# SCH_chris-dual-hd-connector-v3_2021-12-0.net
KiCad netlist of a schematic drawn in EasyEDA
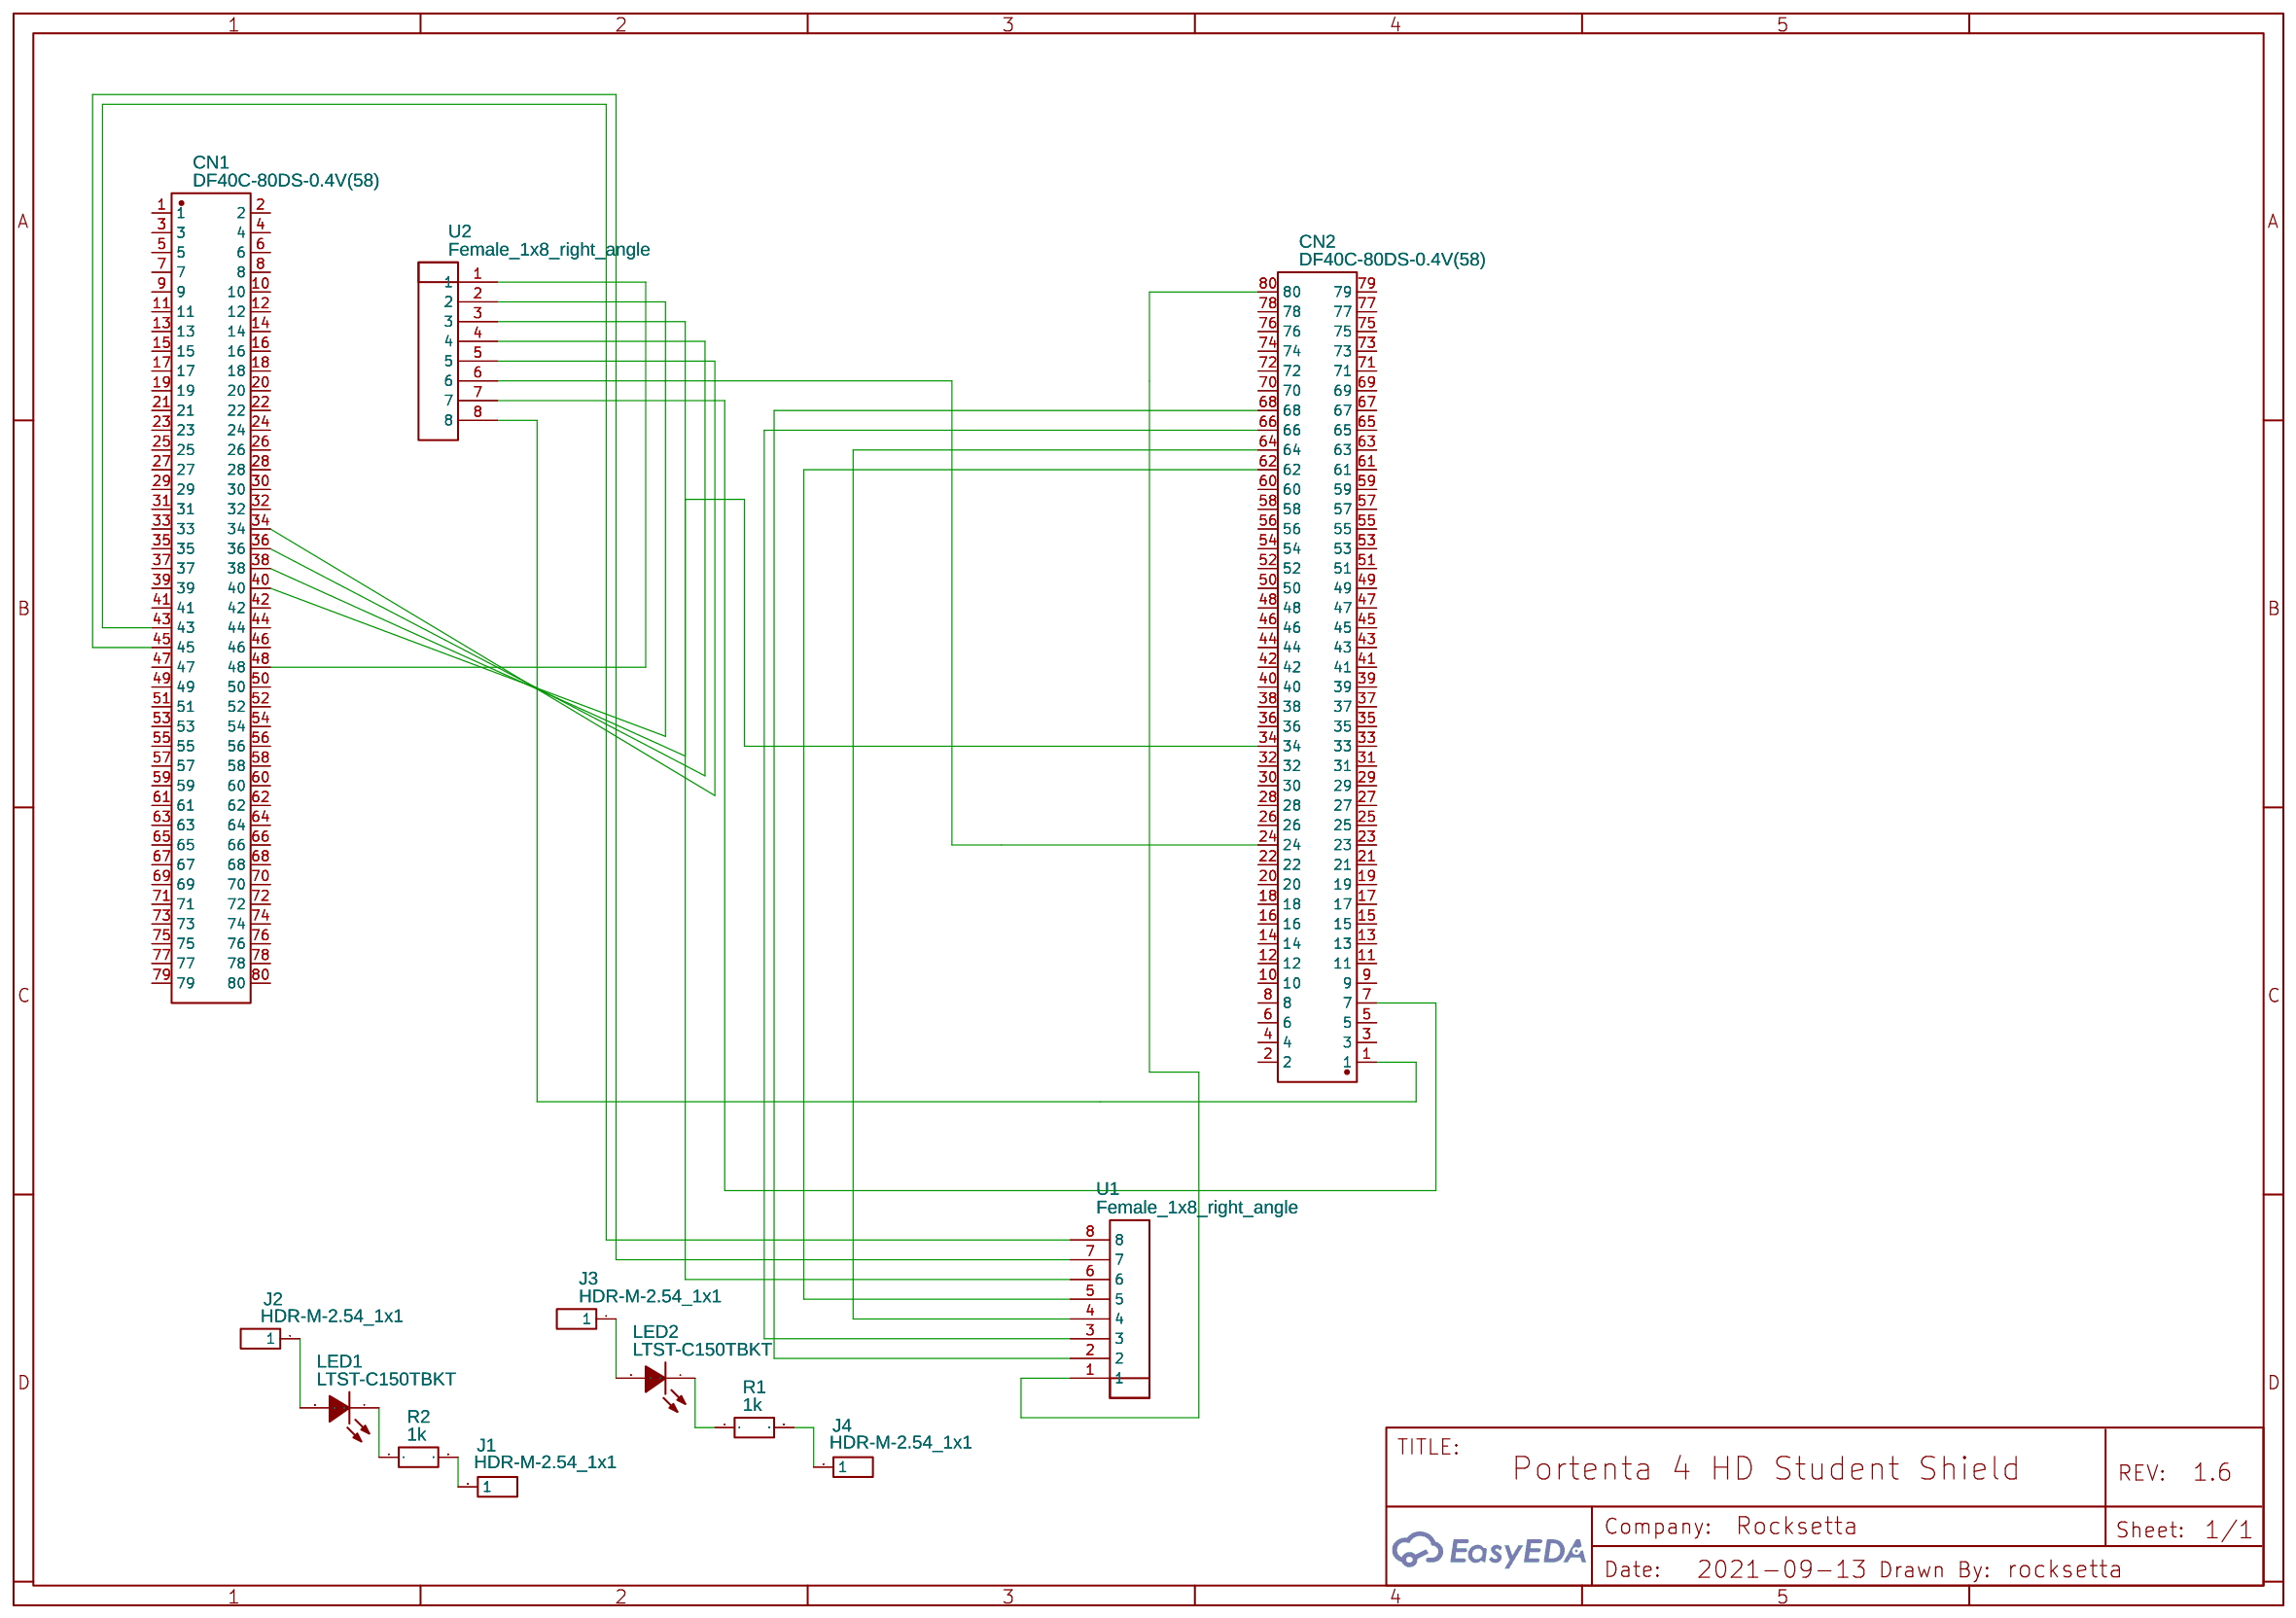
[diagram p0: schematic sheet]

(export (version "E")
  (design (tool "Eeschema 10.0.6"))
  (components
    (comp (ref "CN1")
      (value "DF40C-80DS-0.4V(58)")
      (fields (field (name "BOM_Supplier Part") "C597941"))
      (libsource (lib "") (part "DF40C-80DS-0.4V(58)_1"))
    )
    (comp (ref "CN2")
      (value "DF40C-80DS-0.4V(58)")
      (fields (field (name "BOM_Supplier Part") "C597941"))
      (libsource (lib "") (part "DF40C-80DS-0.4V(58)"))
    )
    (comp (ref "J1")
      (value "HDR-M-2.54_1x1")
      (fields (field (name "BOM_Supplier Part") "C81276"))
      (libsource (lib "") (part "HDR-M-2.54_1x1"))
    )
    (comp (ref "J2")
      (value "HDR-M-2.54_1x1")
      (fields (field (name "BOM_Supplier Part") "C81276"))
      (libsource (lib "") (part "HDR-M-2.54_1x1_1"))
    )
    (comp (ref "J3")
      (value "HDR-M-2.54_1x1")
      (fields (field (name "BOM_Supplier Part") "C81276"))
      (libsource (lib "") (part "HDR-M-2.54_1x1_1"))
    )
    (comp (ref "J4")
      (value "HDR-M-2.54_1x1")
      (fields (field (name "BOM_Supplier Part") "C81276"))
      (libsource (lib "") (part "HDR-M-2.54_1x1"))
    )
    (comp (ref "LED1")
      (value "LTST-C150TBKT")
      (fields (field (name "BOM_Supplier Part") "C125088"))
      (libsource (lib "") (part "LTST-C150TBKT"))
    )
    (comp (ref "LED2")
      (value "LTST-C150TBKT")
      (fields (field (name "BOM_Supplier Part") "C125088"))
      (libsource (lib "") (part "LTST-C150TBKT"))
    )
    (comp (ref "R1") (value "1k") (libsource (lib "") (part "R_0805_EU")))
    (comp (ref "R2") (value "1k") (libsource (lib "") (part "R_0805_EU")))
    (comp (ref "U1")
      (value "Female_1x8_right_angle")
      (fields
        (field (name "BOM_Manufacturer Part") "PPPC081LGBN-RC")
        (field (name "BOM_Supplier Part") "S5483-ND")
      )
      (libsource (lib "") (part "Female_1x8_right_angle_1"))
    )
    (comp (ref "U2")
      (value "Female_1x8_right_angle")
      (fields
        (field (name "BOM_Manufacturer Part") "PPPC081LGBN-RC")
        (field (name "BOM_Supplier Part") "S5483-ND")
      )
      (libsource (lib "") (part "Female_1x8_right_angle"))
    )
  )
  (nets
    (net (code "1") (name "Net-(CN1-Pad34)") (class "Default")
      (node (ref "CN1") (pin "34") (pinfunction "34_34") (pintype "unspecified"))
      (node (ref "U2") (pin "5") (pinfunction "5_5") (pintype "unspecified"))
    )
    (net (code "2") (name "Net-(CN1-Pad36)") (class "Default")
      (node (ref "CN1") (pin "36") (pinfunction "36_36") (pintype "unspecified"))
      (node (ref "U2") (pin "4") (pinfunction "4_4") (pintype "unspecified"))
    )
    (net (code "3") (name "Net-(CN1-Pad38)") (class "Default")
      (node (ref "CN1") (pin "38") (pinfunction "38_38") (pintype "unspecified"))
      (node (ref "U2") (pin "3") (pinfunction "3_3") (pintype "unspecified"))
    )
    (net (code "4") (name "Net-(CN1-Pad40)") (class "Default")
      (node (ref "CN1") (pin "40") (pinfunction "40_40") (pintype "unspecified"))
      (node (ref "U2") (pin "2") (pinfunction "2_2") (pintype "unspecified"))
    )
    (net (code "5") (name "Net-(CN1-Pad43)") (class "Default")
      (node (ref "CN1") (pin "43") (pinfunction "43_43") (pintype "unspecified"))
      (node (ref "U1") (pin "8") (pinfunction "8_8") (pintype "unspecified"))
    )
    (net (code "6") (name "Net-(CN1-Pad45)") (class "Default")
      (node (ref "CN1") (pin "45") (pinfunction "45_45") (pintype "unspecified"))
      (node (ref "U1") (pin "7") (pinfunction "7_7") (pintype "unspecified"))
    )
    (net (code "7") (name "Net-(CN1-Pad48)") (class "Default")
      (node (ref "CN1") (pin "48") (pinfunction "48_48") (pintype "unspecified"))
      (node (ref "U2") (pin "1") (pinfunction "1_1") (pintype "unspecified"))
    )
    (net (code "8") (name "Net-(CN2-Pad1)") (class "Default")
      (node (ref "CN2") (pin "1") (pinfunction "1_1") (pintype "unspecified"))
      (node (ref "U2") (pin "8") (pinfunction "8_8") (pintype "unspecified"))
    )
    (net (code "9") (name "Net-(CN2-Pad7)") (class "Default")
      (node (ref "CN2") (pin "7") (pinfunction "7_7") (pintype "unspecified"))
      (node (ref "U2") (pin "7") (pinfunction "7_7") (pintype "unspecified"))
    )
    (net (code "10") (name "Net-(CN2-Pad24)") (class "Default")
      (node (ref "CN2") (pin "24") (pinfunction "24_24") (pintype "unspecified"))
      (node (ref "U2") (pin "6") (pinfunction "6_6") (pintype "unspecified"))
    )
    (net (code "11") (name "Net-(CN2-Pad34)") (class "Default")
      (node (ref "CN2") (pin "34") (pinfunction "34_34") (pintype "unspecified"))
      (node (ref "U1") (pin "6") (pinfunction "6_6") (pintype "unspecified"))
    )
    (net (code "12") (name "Net-(CN2-Pad62)") (class "Default")
      (node (ref "CN2") (pin "62") (pinfunction "62_62") (pintype "unspecified"))
      (node (ref "U1") (pin "5") (pinfunction "5_5") (pintype "unspecified"))
    )
    (net (code "13") (name "Net-(CN2-Pad64)") (class "Default")
      (node (ref "CN2") (pin "64") (pinfunction "64_64") (pintype "unspecified"))
      (node (ref "U1") (pin "4") (pinfunction "4_4") (pintype "unspecified"))
    )
    (net (code "14") (name "Net-(CN2-Pad66)") (class "Default")
      (node (ref "CN2") (pin "66") (pinfunction "66_66") (pintype "unspecified"))
      (node (ref "U1") (pin "3") (pinfunction "3_3") (pintype "unspecified"))
    )
    (net (code "15") (name "Net-(CN2-Pad68)") (class "Default")
      (node (ref "CN2") (pin "68") (pinfunction "68_68") (pintype "unspecified"))
      (node (ref "U1") (pin "2") (pinfunction "2_2") (pintype "unspecified"))
    )
    (net (code "16") (name "Net-(CN2-Pad80)") (class "Default")
      (node (ref "CN2") (pin "80") (pinfunction "80_80") (pintype "unspecified"))
      (node (ref "U1") (pin "1") (pinfunction "1_1") (pintype "unspecified"))
    )
    (net (code "17") (name "Net-(J1-Pad1)") (class "Default")
      (node (ref "J1") (pin "1") (pinfunction "1_1") (pintype "input"))
      (node (ref "R2") (pin "2") (pinfunction "2_2") (pintype "unspecified"))
    )
    (net (code "18") (name "Net-(J4-Pad1)") (class "Default")
      (node (ref "J4") (pin "1") (pinfunction "1_1") (pintype "input"))
      (node (ref "R1") (pin "2") (pinfunction "2_2") (pintype "unspecified"))
    )
    (net (code "19") (name "Net-(LED1-A)") (class "Default")
      (node (ref "J2") (pin "1") (pinfunction "1_1") (pintype "input"))
      (node (ref "LED1") (pin "2") (pinfunction "A_2") (pintype "unspecified"))
    )
    (net (code "20") (name "Net-(LED1-K)") (class "Default")
      (node (ref "LED1") (pin "1") (pinfunction "K_1") (pintype "unspecified"))
      (node (ref "R2") (pin "1") (pinfunction "1_1") (pintype "unspecified"))
    )
    (net (code "21") (name "Net-(LED2-A)") (class "Default")
      (node (ref "J3") (pin "1") (pinfunction "1_1") (pintype "input"))
      (node (ref "LED2") (pin "2") (pinfunction "A_2") (pintype "unspecified"))
    )
    (net (code "22") (name "Net-(LED2-K)") (class "Default")
      (node (ref "LED2") (pin "1") (pinfunction "K_1") (pintype "unspecified"))
      (node (ref "R1") (pin "1") (pinfunction "1_1") (pintype "unspecified"))
    )
    (net (code "23") (name "unconnected-(CN1-Pad1)") (class "Default")
      (node (ref "CN1") (pin "1") (pinfunction "1_1") (pintype "unspecified"))
    )
    (net (code "24") (name "unconnected-(CN1-Pad2)") (class "Default")
      (node (ref "CN1") (pin "2") (pinfunction "2_2") (pintype "unspecified"))
    )
    (net (code "25") (name "unconnected-(CN1-Pad3)") (class "Default")
      (node (ref "CN1") (pin "3") (pinfunction "3_3") (pintype "unspecified"))
    )
    (net (code "26") (name "unconnected-(CN1-Pad4)") (class "Default")
      (node (ref "CN1") (pin "4") (pinfunction "4_4") (pintype "unspecified"))
    )
    (net (code "27") (name "unconnected-(CN1-Pad5)") (class "Default")
      (node (ref "CN1") (pin "5") (pinfunction "5_5") (pintype "unspecified"))
    )
    (net (code "28") (name "unconnected-(CN1-Pad6)") (class "Default")
      (node (ref "CN1") (pin "6") (pinfunction "6_6") (pintype "unspecified"))
    )
    (net (code "29") (name "unconnected-(CN1-Pad7)") (class "Default")
      (node (ref "CN1") (pin "7") (pinfunction "7_7") (pintype "unspecified"))
    )
    (net (code "30") (name "unconnected-(CN1-Pad8)") (class "Default")
      (node (ref "CN1") (pin "8") (pinfunction "8_8") (pintype "unspecified"))
    )
    (net (code "31") (name "unconnected-(CN1-Pad9)") (class "Default")
      (node (ref "CN1") (pin "9") (pinfunction "9_9") (pintype "unspecified"))
    )
    (net (code "32") (name "unconnected-(CN1-Pad10)") (class "Default")
      (node (ref "CN1") (pin "10") (pinfunction "10_10") (pintype "unspecified"))
    )
    (net (code "33") (name "unconnected-(CN1-Pad11)") (class "Default")
      (node (ref "CN1") (pin "11") (pinfunction "11_11") (pintype "unspecified"))
    )
    (net (code "34") (name "unconnected-(CN1-Pad12)") (class "Default")
      (node (ref "CN1") (pin "12") (pinfunction "12_12") (pintype "unspecified"))
    )
    (net (code "35") (name "unconnected-(CN1-Pad13)") (class "Default")
      (node (ref "CN1") (pin "13") (pinfunction "13_13") (pintype "unspecified"))
    )
    (net (code "36") (name "unconnected-(CN1-Pad14)") (class "Default")
      (node (ref "CN1") (pin "14") (pinfunction "14_14") (pintype "unspecified"))
    )
    (net (code "37") (name "unconnected-(CN1-Pad15)") (class "Default")
      (node (ref "CN1") (pin "15") (pinfunction "15_15") (pintype "unspecified"))
    )
    (net (code "38") (name "unconnected-(CN1-Pad16)") (class "Default")
      (node (ref "CN1") (pin "16") (pinfunction "16_16") (pintype "unspecified"))
    )
    (net (code "39") (name "unconnected-(CN1-Pad17)") (class "Default")
      (node (ref "CN1") (pin "17") (pinfunction "17_17") (pintype "unspecified"))
    )
    (net (code "40") (name "unconnected-(CN1-Pad18)") (class "Default")
      (node (ref "CN1") (pin "18") (pinfunction "18_18") (pintype "unspecified"))
    )
    (net (code "41") (name "unconnected-(CN1-Pad19)") (class "Default")
      (node (ref "CN1") (pin "19") (pinfunction "19_19") (pintype "unspecified"))
    )
    (net (code "42") (name "unconnected-(CN1-Pad20)") (class "Default")
      (node (ref "CN1") (pin "20") (pinfunction "20_20") (pintype "unspecified"))
    )
    (net (code "43") (name "unconnected-(CN1-Pad21)") (class "Default")
      (node (ref "CN1") (pin "21") (pinfunction "21_21") (pintype "unspecified"))
    )
    (net (code "44") (name "unconnected-(CN1-Pad22)") (class "Default")
      (node (ref "CN1") (pin "22") (pinfunction "22_22") (pintype "unspecified"))
    )
    (net (code "45") (name "unconnected-(CN1-Pad23)") (class "Default")
      (node (ref "CN1") (pin "23") (pinfunction "23_23") (pintype "unspecified"))
    )
    (net (code "46") (name "unconnected-(CN1-Pad24)") (class "Default")
      (node (ref "CN1") (pin "24") (pinfunction "24_24") (pintype "unspecified"))
    )
    (net (code "47") (name "unconnected-(CN1-Pad25)") (class "Default")
      (node (ref "CN1") (pin "25") (pinfunction "25_25") (pintype "unspecified"))
    )
    (net (code "48") (name "unconnected-(CN1-Pad26)") (class "Default")
      (node (ref "CN1") (pin "26") (pinfunction "26_26") (pintype "unspecified"))
    )
    (net (code "49") (name "unconnected-(CN1-Pad27)") (class "Default")
      (node (ref "CN1") (pin "27") (pinfunction "27_27") (pintype "unspecified"))
    )
    (net (code "50") (name "unconnected-(CN1-Pad28)") (class "Default")
      (node (ref "CN1") (pin "28") (pinfunction "28_28") (pintype "unspecified"))
    )
    (net (code "51") (name "unconnected-(CN1-Pad29)") (class "Default")
      (node (ref "CN1") (pin "29") (pinfunction "29_29") (pintype "unspecified"))
    )
    (net (code "52") (name "unconnected-(CN1-Pad30)") (class "Default")
      (node (ref "CN1") (pin "30") (pinfunction "30_30") (pintype "unspecified"))
    )
    (net (code "53") (name "unconnected-(CN1-Pad31)") (class "Default")
      (node (ref "CN1") (pin "31") (pinfunction "31_31") (pintype "unspecified"))
    )
    (net (code "54") (name "unconnected-(CN1-Pad32)") (class "Default")
      (node (ref "CN1") (pin "32") (pinfunction "32_32") (pintype "unspecified"))
    )
    (net (code "55") (name "unconnected-(CN1-Pad33)") (class "Default")
      (node (ref "CN1") (pin "33") (pinfunction "33_33") (pintype "unspecified"))
    )
    (net (code "56") (name "unconnected-(CN1-Pad35)") (class "Default")
      (node (ref "CN1") (pin "35") (pinfunction "35_35") (pintype "unspecified"))
    )
    (net (code "57") (name "unconnected-(CN1-Pad37)") (class "Default")
      (node (ref "CN1") (pin "37") (pinfunction "37_37") (pintype "unspecified"))
    )
    (net (code "58") (name "unconnected-(CN1-Pad39)") (class "Default")
      (node (ref "CN1") (pin "39") (pinfunction "39_39") (pintype "unspecified"))
    )
    (net (code "59") (name "unconnected-(CN1-Pad41)") (class "Default")
      (node (ref "CN1") (pin "41") (pinfunction "41_41") (pintype "unspecified"))
    )
    (net (code "60") (name "unconnected-(CN1-Pad42)") (class "Default")
      (node (ref "CN1") (pin "42") (pinfunction "42_42") (pintype "unspecified"))
    )
    (net (code "61") (name "unconnected-(CN1-Pad44)") (class "Default")
      (node (ref "CN1") (pin "44") (pinfunction "44_44") (pintype "unspecified"))
    )
    (net (code "62") (name "unconnected-(CN1-Pad46)") (class "Default")
      (node (ref "CN1") (pin "46") (pinfunction "46_46") (pintype "unspecified"))
    )
    (net (code "63") (name "unconnected-(CN1-Pad47)") (class "Default")
      (node (ref "CN1") (pin "47") (pinfunction "47_47") (pintype "unspecified"))
    )
    (net (code "64") (name "unconnected-(CN1-Pad49)") (class "Default")
      (node (ref "CN1") (pin "49") (pinfunction "49_49") (pintype "unspecified"))
    )
    (net (code "65") (name "unconnected-(CN1-Pad50)") (class "Default")
      (node (ref "CN1") (pin "50") (pinfunction "50_50") (pintype "unspecified"))
    )
    (net (code "66") (name "unconnected-(CN1-Pad51)") (class "Default")
      (node (ref "CN1") (pin "51") (pinfunction "51_51") (pintype "unspecified"))
    )
    (net (code "67") (name "unconnected-(CN1-Pad52)") (class "Default")
      (node (ref "CN1") (pin "52") (pinfunction "52_52") (pintype "unspecified"))
    )
    (net (code "68") (name "unconnected-(CN1-Pad53)") (class "Default")
      (node (ref "CN1") (pin "53") (pinfunction "53_53") (pintype "unspecified"))
    )
    (net (code "69") (name "unconnected-(CN1-Pad54)") (class "Default")
      (node (ref "CN1") (pin "54") (pinfunction "54_54") (pintype "unspecified"))
    )
    (net (code "70") (name "unconnected-(CN1-Pad55)") (class "Default")
      (node (ref "CN1") (pin "55") (pinfunction "55_55") (pintype "unspecified"))
    )
    (net (code "71") (name "unconnected-(CN1-Pad56)") (class "Default")
      (node (ref "CN1") (pin "56") (pinfunction "56_56") (pintype "unspecified"))
    )
    (net (code "72") (name "unconnected-(CN1-Pad57)") (class "Default")
      (node (ref "CN1") (pin "57") (pinfunction "57_57") (pintype "unspecified"))
    )
    (net (code "73") (name "unconnected-(CN1-Pad58)") (class "Default")
      (node (ref "CN1") (pin "58") (pinfunction "58_58") (pintype "unspecified"))
    )
    (net (code "74") (name "unconnected-(CN1-Pad59)") (class "Default")
      (node (ref "CN1") (pin "59") (pinfunction "59_59") (pintype "unspecified"))
    )
    (net (code "75") (name "unconnected-(CN1-Pad60)") (class "Default")
      (node (ref "CN1") (pin "60") (pinfunction "60_60") (pintype "unspecified"))
    )
    (net (code "76") (name "unconnected-(CN1-Pad61)") (class "Default")
      (node (ref "CN1") (pin "61") (pinfunction "61_61") (pintype "unspecified"))
    )
    (net (code "77") (name "unconnected-(CN1-Pad62)") (class "Default")
      (node (ref "CN1") (pin "62") (pinfunction "62_62") (pintype "unspecified"))
    )
    (net (code "78") (name "unconnected-(CN1-Pad63)") (class "Default")
      (node (ref "CN1") (pin "63") (pinfunction "63_63") (pintype "unspecified"))
    )
    (net (code "79") (name "unconnected-(CN1-Pad64)") (class "Default")
      (node (ref "CN1") (pin "64") (pinfunction "64_64") (pintype "unspecified"))
    )
    (net (code "80") (name "unconnected-(CN1-Pad65)") (class "Default")
      (node (ref "CN1") (pin "65") (pinfunction "65_65") (pintype "unspecified"))
    )
    (net (code "81") (name "unconnected-(CN1-Pad66)") (class "Default")
      (node (ref "CN1") (pin "66") (pinfunction "66_66") (pintype "unspecified"))
    )
    (net (code "82") (name "unconnected-(CN1-Pad67)") (class "Default")
      (node (ref "CN1") (pin "67") (pinfunction "67_67") (pintype "unspecified"))
    )
    (net (code "83") (name "unconnected-(CN1-Pad68)") (class "Default")
      (node (ref "CN1") (pin "68") (pinfunction "68_68") (pintype "unspecified"))
    )
    (net (code "84") (name "unconnected-(CN1-Pad69)") (class "Default")
      (node (ref "CN1") (pin "69") (pinfunction "69_69") (pintype "unspecified"))
    )
    (net (code "85") (name "unconnected-(CN1-Pad70)") (class "Default")
      (node (ref "CN1") (pin "70") (pinfunction "70_70") (pintype "unspecified"))
    )
    (net (code "86") (name "unconnected-(CN1-Pad71)") (class "Default")
      (node (ref "CN1") (pin "71") (pinfunction "71_71") (pintype "unspecified"))
    )
    (net (code "87") (name "unconnected-(CN1-Pad72)") (class "Default")
      (node (ref "CN1") (pin "72") (pinfunction "72_72") (pintype "unspecified"))
    )
    (net (code "88") (name "unconnected-(CN1-Pad73)") (class "Default")
      (node (ref "CN1") (pin "73") (pinfunction "73_73") (pintype "unspecified"))
    )
    (net (code "89") (name "unconnected-(CN1-Pad74)") (class "Default")
      (node (ref "CN1") (pin "74") (pinfunction "74_74") (pintype "unspecified"))
    )
    (net (code "90") (name "unconnected-(CN1-Pad75)") (class "Default")
      (node (ref "CN1") (pin "75") (pinfunction "75_75") (pintype "unspecified"))
    )
    (net (code "91") (name "unconnected-(CN1-Pad76)") (class "Default")
      (node (ref "CN1") (pin "76") (pinfunction "76_76") (pintype "unspecified"))
    )
    (net (code "92") (name "unconnected-(CN1-Pad77)") (class "Default")
      (node (ref "CN1") (pin "77") (pinfunction "77_77") (pintype "unspecified"))
    )
    (net (code "93") (name "unconnected-(CN1-Pad78)") (class "Default")
      (node (ref "CN1") (pin "78") (pinfunction "78_78") (pintype "unspecified"))
    )
    (net (code "94") (name "unconnected-(CN1-Pad79)") (class "Default")
      (node (ref "CN1") (pin "79") (pinfunction "79_79") (pintype "unspecified"))
    )
    (net (code "95") (name "unconnected-(CN1-Pad80)") (class "Default")
      (node (ref "CN1") (pin "80") (pinfunction "80_80") (pintype "unspecified"))
    )
    (net (code "96") (name "unconnected-(CN2-Pad2)") (class "Default")
      (node (ref "CN2") (pin "2") (pinfunction "2_2") (pintype "unspecified"))
    )
    (net (code "97") (name "unconnected-(CN2-Pad3)") (class "Default")
      (node (ref "CN2") (pin "3") (pinfunction "3_3") (pintype "unspecified"))
    )
    (net (code "98") (name "unconnected-(CN2-Pad4)") (class "Default")
      (node (ref "CN2") (pin "4") (pinfunction "4_4") (pintype "unspecified"))
    )
    (net (code "99") (name "unconnected-(CN2-Pad5)") (class "Default")
      (node (ref "CN2") (pin "5") (pinfunction "5_5") (pintype "unspecified"))
    )
    (net (code "100") (name "unconnected-(CN2-Pad6)") (class "Default")
      (node (ref "CN2") (pin "6") (pinfunction "6_6") (pintype "unspecified"))
    )
    (net (code "101") (name "unconnected-(CN2-Pad8)") (class "Default")
      (node (ref "CN2") (pin "8") (pinfunction "8_8") (pintype "unspecified"))
    )
    (net (code "102") (name "unconnected-(CN2-Pad9)") (class "Default")
      (node (ref "CN2") (pin "9") (pinfunction "9_9") (pintype "unspecified"))
    )
    (net (code "103") (name "unconnected-(CN2-Pad10)") (class "Default")
      (node (ref "CN2") (pin "10") (pinfunction "10_10") (pintype "unspecified"))
    )
    (net (code "104") (name "unconnected-(CN2-Pad11)") (class "Default")
      (node (ref "CN2") (pin "11") (pinfunction "11_11") (pintype "unspecified"))
    )
    (net (code "105") (name "unconnected-(CN2-Pad12)") (class "Default")
      (node (ref "CN2") (pin "12") (pinfunction "12_12") (pintype "unspecified"))
    )
    (net (code "106") (name "unconnected-(CN2-Pad13)") (class "Default")
      (node (ref "CN2") (pin "13") (pinfunction "13_13") (pintype "unspecified"))
    )
    (net (code "107") (name "unconnected-(CN2-Pad14)") (class "Default")
      (node (ref "CN2") (pin "14") (pinfunction "14_14") (pintype "unspecified"))
    )
    (net (code "108") (name "unconnected-(CN2-Pad15)") (class "Default")
      (node (ref "CN2") (pin "15") (pinfunction "15_15") (pintype "unspecified"))
    )
    (net (code "109") (name "unconnected-(CN2-Pad16)") (class "Default")
      (node (ref "CN2") (pin "16") (pinfunction "16_16") (pintype "unspecified"))
    )
    (net (code "110") (name "unconnected-(CN2-Pad17)") (class "Default")
      (node (ref "CN2") (pin "17") (pinfunction "17_17") (pintype "unspecified"))
    )
    (net (code "111") (name "unconnected-(CN2-Pad18)") (class "Default")
      (node (ref "CN2") (pin "18") (pinfunction "18_18") (pintype "unspecified"))
    )
    (net (code "112") (name "unconnected-(CN2-Pad19)") (class "Default")
      (node (ref "CN2") (pin "19") (pinfunction "19_19") (pintype "unspecified"))
    )
    (net (code "113") (name "unconnected-(CN2-Pad20)") (class "Default")
      (node (ref "CN2") (pin "20") (pinfunction "20_20") (pintype "unspecified"))
    )
    (net (code "114") (name "unconnected-(CN2-Pad21)") (class "Default")
      (node (ref "CN2") (pin "21") (pinfunction "21_21") (pintype "unspecified"))
    )
    (net (code "115") (name "unconnected-(CN2-Pad22)") (class "Default")
      (node (ref "CN2") (pin "22") (pinfunction "22_22") (pintype "unspecified"))
    )
    (net (code "116") (name "unconnected-(CN2-Pad23)") (class "Default")
      (node (ref "CN2") (pin "23") (pinfunction "23_23") (pintype "unspecified"))
    )
    (net (code "117") (name "unconnected-(CN2-Pad25)") (class "Default")
      (node (ref "CN2") (pin "25") (pinfunction "25_25") (pintype "unspecified"))
    )
    (net (code "118") (name "unconnected-(CN2-Pad26)") (class "Default")
      (node (ref "CN2") (pin "26") (pinfunction "26_26") (pintype "unspecified"))
    )
    (net (code "119") (name "unconnected-(CN2-Pad27)") (class "Default")
      (node (ref "CN2") (pin "27") (pinfunction "27_27") (pintype "unspecified"))
    )
    (net (code "120") (name "unconnected-(CN2-Pad28)") (class "Default")
      (node (ref "CN2") (pin "28") (pinfunction "28_28") (pintype "unspecified"))
    )
    (net (code "121") (name "unconnected-(CN2-Pad29)") (class "Default")
      (node (ref "CN2") (pin "29") (pinfunction "29_29") (pintype "unspecified"))
    )
    (net (code "122") (name "unconnected-(CN2-Pad30)") (class "Default")
      (node (ref "CN2") (pin "30") (pinfunction "30_30") (pintype "unspecified"))
    )
    (net (code "123") (name "unconnected-(CN2-Pad31)") (class "Default")
      (node (ref "CN2") (pin "31") (pinfunction "31_31") (pintype "unspecified"))
    )
    (net (code "124") (name "unconnected-(CN2-Pad32)") (class "Default")
      (node (ref "CN2") (pin "32") (pinfunction "32_32") (pintype "unspecified"))
    )
    (net (code "125") (name "unconnected-(CN2-Pad33)") (class "Default")
      (node (ref "CN2") (pin "33") (pinfunction "33_33") (pintype "unspecified"))
    )
    (net (code "126") (name "unconnected-(CN2-Pad35)") (class "Default")
      (node (ref "CN2") (pin "35") (pinfunction "35_35") (pintype "unspecified"))
    )
    (net (code "127") (name "unconnected-(CN2-Pad36)") (class "Default")
      (node (ref "CN2") (pin "36") (pinfunction "36_36") (pintype "unspecified"))
    )
    (net (code "128") (name "unconnected-(CN2-Pad37)") (class "Default")
      (node (ref "CN2") (pin "37") (pinfunction "37_37") (pintype "unspecified"))
    )
    (net (code "129") (name "unconnected-(CN2-Pad38)") (class "Default")
      (node (ref "CN2") (pin "38") (pinfunction "38_38") (pintype "unspecified"))
    )
    (net (code "130") (name "unconnected-(CN2-Pad39)") (class "Default")
      (node (ref "CN2") (pin "39") (pinfunction "39_39") (pintype "unspecified"))
    )
    (net (code "131") (name "unconnected-(CN2-Pad40)") (class "Default")
      (node (ref "CN2") (pin "40") (pinfunction "40_40") (pintype "unspecified"))
    )
    (net (code "132") (name "unconnected-(CN2-Pad41)") (class "Default")
      (node (ref "CN2") (pin "41") (pinfunction "41_41") (pintype "unspecified"))
    )
    (net (code "133") (name "unconnected-(CN2-Pad42)") (class "Default")
      (node (ref "CN2") (pin "42") (pinfunction "42_42") (pintype "unspecified"))
    )
    (net (code "134") (name "unconnected-(CN2-Pad43)") (class "Default")
      (node (ref "CN2") (pin "43") (pinfunction "43_43") (pintype "unspecified"))
    )
    (net (code "135") (name "unconnected-(CN2-Pad44)") (class "Default")
      (node (ref "CN2") (pin "44") (pinfunction "44_44") (pintype "unspecified"))
    )
    (net (code "136") (name "unconnected-(CN2-Pad45)") (class "Default")
      (node (ref "CN2") (pin "45") (pinfunction "45_45") (pintype "unspecified"))
    )
    (net (code "137") (name "unconnected-(CN2-Pad46)") (class "Default")
      (node (ref "CN2") (pin "46") (pinfunction "46_46") (pintype "unspecified"))
    )
    (net (code "138") (name "unconnected-(CN2-Pad47)") (class "Default")
      (node (ref "CN2") (pin "47") (pinfunction "47_47") (pintype "unspecified"))
    )
    (net (code "139") (name "unconnected-(CN2-Pad48)") (class "Default")
      (node (ref "CN2") (pin "48") (pinfunction "48_48") (pintype "unspecified"))
    )
    (net (code "140") (name "unconnected-(CN2-Pad49)") (class "Default")
      (node (ref "CN2") (pin "49") (pinfunction "49_49") (pintype "unspecified"))
    )
    (net (code "141") (name "unconnected-(CN2-Pad50)") (class "Default")
      (node (ref "CN2") (pin "50") (pinfunction "50_50") (pintype "unspecified"))
    )
    (net (code "142") (name "unconnected-(CN2-Pad51)") (class "Default")
      (node (ref "CN2") (pin "51") (pinfunction "51_51") (pintype "unspecified"))
    )
    (net (code "143") (name "unconnected-(CN2-Pad52)") (class "Default")
      (node (ref "CN2") (pin "52") (pinfunction "52_52") (pintype "unspecified"))
    )
    (net (code "144") (name "unconnected-(CN2-Pad53)") (class "Default")
      (node (ref "CN2") (pin "53") (pinfunction "53_53") (pintype "unspecified"))
    )
    (net (code "145") (name "unconnected-(CN2-Pad54)") (class "Default")
      (node (ref "CN2") (pin "54") (pinfunction "54_54") (pintype "unspecified"))
    )
    (net (code "146") (name "unconnected-(CN2-Pad55)") (class "Default")
      (node (ref "CN2") (pin "55") (pinfunction "55_55") (pintype "unspecified"))
    )
    (net (code "147") (name "unconnected-(CN2-Pad56)") (class "Default")
      (node (ref "CN2") (pin "56") (pinfunction "56_56") (pintype "unspecified"))
    )
    (net (code "148") (name "unconnected-(CN2-Pad57)") (class "Default")
      (node (ref "CN2") (pin "57") (pinfunction "57_57") (pintype "unspecified"))
    )
    (net (code "149") (name "unconnected-(CN2-Pad58)") (class "Default")
      (node (ref "CN2") (pin "58") (pinfunction "58_58") (pintype "unspecified"))
    )
    (net (code "150") (name "unconnected-(CN2-Pad59)") (class "Default")
      (node (ref "CN2") (pin "59") (pinfunction "59_59") (pintype "unspecified"))
    )
    (net (code "151") (name "unconnected-(CN2-Pad60)") (class "Default")
      (node (ref "CN2") (pin "60") (pinfunction "60_60") (pintype "unspecified"))
    )
    (net (code "152") (name "unconnected-(CN2-Pad61)") (class "Default")
      (node (ref "CN2") (pin "61") (pinfunction "61_61") (pintype "unspecified"))
    )
    (net (code "153") (name "unconnected-(CN2-Pad63)") (class "Default")
      (node (ref "CN2") (pin "63") (pinfunction "63_63") (pintype "unspecified"))
    )
    (net (code "154") (name "unconnected-(CN2-Pad65)") (class "Default")
      (node (ref "CN2") (pin "65") (pinfunction "65_65") (pintype "unspecified"))
    )
    (net (code "155") (name "unconnected-(CN2-Pad67)") (class "Default")
      (node (ref "CN2") (pin "67") (pinfunction "67_67") (pintype "unspecified"))
    )
    (net (code "156") (name "unconnected-(CN2-Pad69)") (class "Default")
      (node (ref "CN2") (pin "69") (pinfunction "69_69") (pintype "unspecified"))
    )
    (net (code "157") (name "unconnected-(CN2-Pad70)") (class "Default")
      (node (ref "CN2") (pin "70") (pinfunction "70_70") (pintype "unspecified"))
    )
    (net (code "158") (name "unconnected-(CN2-Pad71)") (class "Default")
      (node (ref "CN2") (pin "71") (pinfunction "71_71") (pintype "unspecified"))
    )
    (net (code "159") (name "unconnected-(CN2-Pad72)") (class "Default")
      (node (ref "CN2") (pin "72") (pinfunction "72_72") (pintype "unspecified"))
    )
    (net (code "160") (name "unconnected-(CN2-Pad73)") (class "Default")
      (node (ref "CN2") (pin "73") (pinfunction "73_73") (pintype "unspecified"))
    )
    (net (code "161") (name "unconnected-(CN2-Pad74)") (class "Default")
      (node (ref "CN2") (pin "74") (pinfunction "74_74") (pintype "unspecified"))
    )
    (net (code "162") (name "unconnected-(CN2-Pad75)") (class "Default")
      (node (ref "CN2") (pin "75") (pinfunction "75_75") (pintype "unspecified"))
    )
    (net (code "163") (name "unconnected-(CN2-Pad76)") (class "Default")
      (node (ref "CN2") (pin "76") (pinfunction "76_76") (pintype "unspecified"))
    )
    (net (code "164") (name "unconnected-(CN2-Pad77)") (class "Default")
      (node (ref "CN2") (pin "77") (pinfunction "77_77") (pintype "unspecified"))
    )
    (net (code "165") (name "unconnected-(CN2-Pad78)") (class "Default")
      (node (ref "CN2") (pin "78") (pinfunction "78_78") (pintype "unspecified"))
    )
    (net (code "166") (name "unconnected-(CN2-Pad79)") (class "Default")
      (node (ref "CN2") (pin "79") (pinfunction "79_79") (pintype "unspecified"))
    )
  )
)
